# 3_waffling80-MX_mcu.net
KiCad netlist of a schematic drawn in Altium Designer
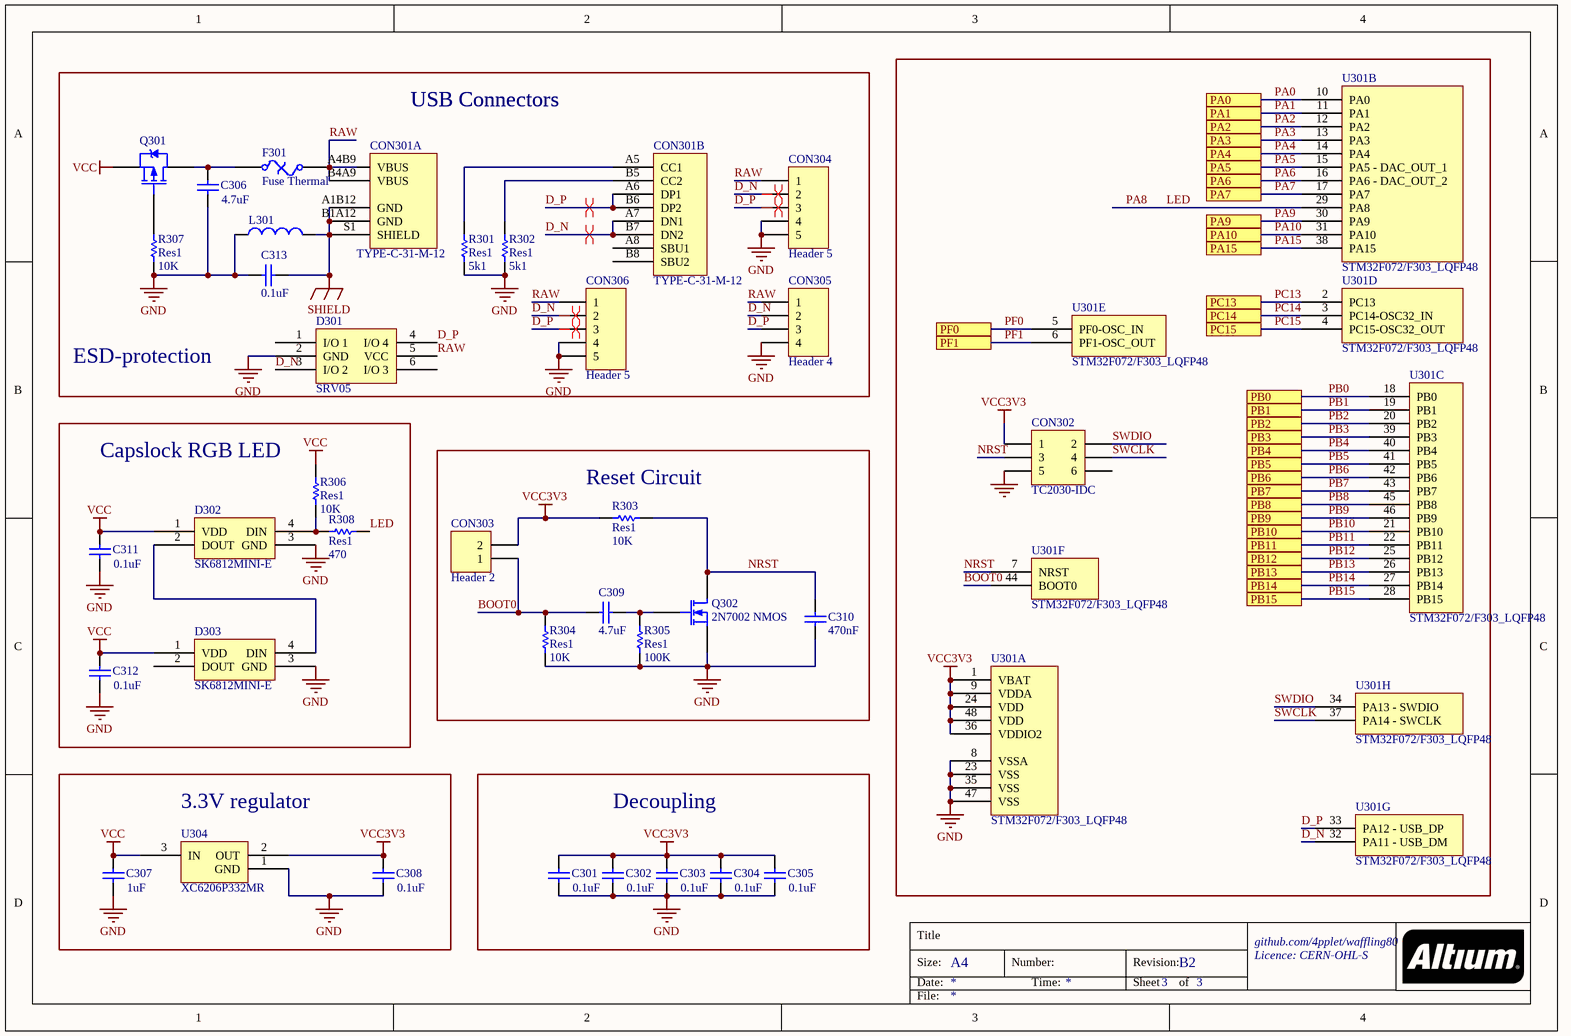
[diagram p0: 3_waffling80-MX_mcu.SchDoc]

(export (version "E")
  (design (tool "Eeschema 10.0.6"))
  (components
    (comp (ref "C301")
      (value "0.1uF")
      (footprint "C0603[1608]")
      (description "Capacitor")
      (fields (field (name "LCSC PART #") "C14663") (field (name "MRF.PART") "CC0603KRX7R9BB104"))
      (libsource (lib "Miscellaneous Devices") (part "Cap"))
    )
    (comp (ref "C302")
      (value "0.1uF")
      (footprint "C0603[1608]")
      (description "Capacitor")
      (fields (field (name "LCSC PART #") "C14663") (field (name "MRF.PART") "CC0603KRX7R9BB104"))
      (libsource (lib "Miscellaneous Devices") (part "Cap"))
    )
    (comp (ref "C303")
      (value "0.1uF")
      (footprint "C0603[1608]")
      (description "Capacitor")
      (fields (field (name "LCSC PART #") "C14663") (field (name "MRF.PART") "CC0603KRX7R9BB104"))
      (libsource (lib "Miscellaneous Devices") (part "Cap"))
    )
    (comp (ref "C304")
      (value "0.1uF")
      (footprint "C0603[1608]")
      (description "Capacitor")
      (fields (field (name "LCSC PART #") "C14663") (field (name "MRF.PART") "CC0603KRX7R9BB104"))
      (libsource (lib "Miscellaneous Devices") (part "Cap"))
    )
    (comp (ref "C305")
      (value "0.1uF")
      (footprint "C0603[1608]")
      (description "Capacitor")
      (fields (field (name "LCSC PART #") "C14663") (field (name "MRF.PART") "CC0603KRX7R9BB104"))
      (libsource (lib "Miscellaneous Devices") (part "Cap"))
    )
    (comp (ref "C306")
      (value "4.7uF")
      (footprint "C0603[1608]")
      (description "Capacitor")
      (fields (field (name "LCSC PART #") "C19666") (field (name "MRF.PART") "CL10A475KO8NNNC"))
      (libsource (lib "Miscellaneous Devices") (part "Cap"))
    )
    (comp (ref "C307")
      (value "1uF")
      (footprint "C0603[1608]")
      (description "Capacitor")
      (fields (field (name "LCSC PART #") "C15849") (field (name "MRF.PART") "CL10A105KB8NNNC"))
      (libsource (lib "Miscellaneous Devices") (part "Cap"))
    )
    (comp (ref "C308")
      (value "0.1uF")
      (footprint "C0603[1608]")
      (description "Capacitor")
      (fields (field (name "LCSC PART #") "C14663") (field (name "MRF.PART") "CC0603KRX7R9BB104"))
      (libsource (lib "Miscellaneous Devices") (part "Cap"))
    )
    (comp (ref "C309")
      (value "4.7uF")
      (footprint "C0603[1608]")
      (description "Capacitor")
      (fields (field (name "LCSC PART #") "C19666") (field (name "MRF.PART") "CL10A475KO8NNNC"))
      (libsource (lib "Miscellaneous Devices") (part "Cap"))
    )
    (comp (ref "C310")
      (value "470nF")
      (footprint "C0603[1608]")
      (description "Capacitor")
      (fields (field (name "LCSC PART #") "C1623") (field (name "MRF.PART") "CL10B474KA8NNNC"))
      (libsource (lib "Miscellaneous Devices") (part "Cap"))
    )
    (comp (ref "C311")
      (value "0.1uF")
      (footprint "C0603[1608]")
      (description "Capacitor")
      (fields (field (name "LCSC PART #") "C14663") (field (name "MRF.PART") "CC0603KRX7R9BB104"))
      (libsource (lib "Miscellaneous Devices") (part "Cap"))
    )
    (comp (ref "C312")
      (value "0.1uF")
      (footprint "C0603[1608]")
      (description "Capacitor")
      (fields (field (name "LCSC PART #") "C14663") (field (name "MRF.PART") "CC0603KRX7R9BB104"))
      (libsource (lib "Miscellaneous Devices") (part "Cap"))
    )
    (comp (ref "C313")
      (value "0.1uF")
      (footprint "C0603[1608]")
      (description "Capacitor")
      (fields (field (name "LCSC PART #") "C14663") (field (name "MRF.PART") "CC0603KRX7R9BB104"))
      (libsource (lib "Miscellaneous Devices") (part "Cap"))
    )
    (comp (ref "CON301")
      (value "TYPE-C-31-M-12")
      (footprint "TYPE-C-31-M-12")
      (fields (field (name "LCSC PART #") "C165948"))
      (libsource (lib "Schlib1") (part "TYPE-C-31-M-12"))
    )
    (comp (ref "CON302")
      (value "TC2030-IDC")
      (footprint "TC2030-IDC-NL")
      (description "Header, 3-Pin, Dual row")
      (libsource (lib "Miscellaneous Connectors") (part "Header 3X2"))
    )
    (comp (ref "CON303")
      (value "Header 2")
      (footprint "HDR1X2")
      (description "Header, 2-Pin")
      (libsource (lib "Miscellaneous Connectors") (part "Header 2"))
    )
    (comp (ref "CON304")
      (value "Header 5")
      (footprint "UDB_combo_JST_MOLEX")
      (description "JST for USB daughter board")
      (fields (field (name "LCSC PART #") "C160404") (field (name "MRF.PART") "SM04B-SRSS-TB(LF)(SN)"))
      (libsource (lib "Miscellaneous Connectors") (part "Header 5"))
    )
    (comp (ref "CON305")
      (value "Header 4")
      (footprint "HDR1X4")
      (description "Header, 4-Pin")
      (libsource (lib "Miscellaneous Connectors") (part "Header 4"))
    )
    (comp (ref "CON306")
      (value "Header 5")
      (footprint "Molex 781710004")
      (description "JST for USB daughter board")
      (fields (field (name "LCSC PART #") "C588524") (field (name "MRF.PART") "781710004"))
      (libsource (lib "Miscellaneous Connectors") (part "Header 5"))
    )
    (comp (ref "D301")
      (value "SRV05")
      (footprint "SOT-23-6")
      (fields (field (name "LCSC PART #") "C85364") (field (name "MRF.PART") "SRV05-4-P-T7"))
      (libsource (lib "Keebs") (part "SRV05"))
    )
    (comp (ref "D302")
      (value "SK6812MINI-E")
      (footprint "SK6812MINI-E - shaped")
      (fields (field (name "LCSC PART #") "C524051") (field (name "MRF.PART") "DY-S352818/RGBC/6812-2T"))
      (libsource (lib "Keebs") (part "SK6812MINI-E"))
    )
    (comp (ref "D303")
      (value "SK6812MINI-E")
      (footprint "SK6812MINI-E - shaped")
      (fields (field (name "LCSC PART #") "C524051") (field (name "MRF.PART") "DY-S352818/RGBC/6812-2T"))
      (libsource (lib "Keebs") (part "SK6812MINI-E"))
    )
    (comp (ref "F301")
      (value "Fuse Thermal")
      (footprint "C1206[3216]")
      (description "Thermal Fuse")
      (fields (field (name "LCSC PART #") "C135338") (field (name "MRF.PART") "ASMD1206-050"))
      (libsource (lib "Miscellaneous Devices") (part "Fuse Thermal"))
    )
    (comp (ref "L301")
      (value "Inductor")
      (footprint "L0805")
      (fields (field (name "LCSC PART #") "C1015") (field (name "MRF.PART") "GZ2012D101TF"))
      (libsource (lib "Simulation Generic Components") (part "Inductor"))
    )
    (comp (ref "Q301")
      (value "PMOS-2")
      (footprint "SOT-23-3")
      (description "P-Channel Power MOSFET")
      (fields (field (name "LCSC PART #") "C10487") (field (name "MRF.PART") "SI2301CDS-T1-GE3"))
      (libsource (lib "Miscellaneous Devices") (part "PMOS-2"))
    )
    (comp (ref "Q302")
      (value "2N7002 NMOS")
      (footprint "SOT-23-3")
      (description "N-Channel MOSFET")
      (fields (field (name "LCSC PART #") "C8545") (field (name "MRF.PART") "2N7002"))
      (libsource (lib "Miscellaneous Devices") (part "MOSFET-N"))
    )
    (comp (ref "R301")
      (value "Res1")
      (footprint "R0603[1608]")
      (description "Resistor")
      (fields
        (field (name "ALTIUM_VALUE") "5k1")
        (field (name "LCSC PART #") "C23186")
        (field (name "MRF.PART") "0603WAF5101T5E")
      )
      (libsource (lib "Miscellaneous Devices") (part "Res1"))
    )
    (comp (ref "R302")
      (value "Res1")
      (footprint "R0603[1608]")
      (description "Resistor")
      (fields
        (field (name "ALTIUM_VALUE") "5k1")
        (field (name "LCSC PART #") "C23186")
        (field (name "MRF.PART") "0603WAF5101T5E")
      )
      (libsource (lib "Miscellaneous Devices") (part "Res1"))
    )
    (comp (ref "R303")
      (value "Res1")
      (footprint "R0603[1608]")
      (description "Resistor")
      (fields
        (field (name "ALTIUM_VALUE") "10K")
        (field (name "LCSC PART #") "C25804")
        (field (name "MRF.PART") "0603WAF1002T5E")
      )
      (libsource (lib "Miscellaneous Devices") (part "Res1"))
    )
    (comp (ref "R304")
      (value "Res1")
      (footprint "R0603[1608]")
      (description "Resistor")
      (fields
        (field (name "ALTIUM_VALUE") "10K")
        (field (name "LCSC PART #") "C25804")
        (field (name "MRF.PART") "0603WAF1002T5E")
      )
      (libsource (lib "Miscellaneous Devices") (part "Res1"))
    )
    (comp (ref "R305")
      (value "Res1")
      (footprint "R0603[1608]")
      (description "Resistor")
      (fields
        (field (name "ALTIUM_VALUE") "100K")
        (field (name "LCSC PART #") "C25803")
        (field (name "MRF.PART") "0603WAF1003T5E")
      )
      (libsource (lib "Miscellaneous Devices") (part "Res1"))
    )
    (comp (ref "R306")
      (value "Res1")
      (footprint "R0603[1608]")
      (description "Resistor")
      (fields
        (field (name "ALTIUM_VALUE") "10K")
        (field (name "LCSC PART #") "C25804")
        (field (name "MRF.PART") "0603WAF1002T5E")
      )
      (libsource (lib "Miscellaneous Devices") (part "Res1"))
    )
    (comp (ref "R307")
      (value "Res1")
      (footprint "R0603[1608]")
      (description "Resistor")
      (fields
        (field (name "ALTIUM_VALUE") "10K")
        (field (name "LCSC PART #") "C25804")
        (field (name "MRF.PART") "0603WAF1002T5E")
      )
      (libsource (lib "Miscellaneous Devices") (part "Res1"))
    )
    (comp (ref "R308")
      (value "Res1")
      (footprint "R0603[1608]")
      (description "Resistor")
      (fields
        (field (name "ALTIUM_VALUE") "470")
        (field (name "LCSC PART #") "C23179")
        (field (name "MRF.PART") "0603WAF4700T5E")
      )
      (libsource (lib "Miscellaneous Devices") (part "Res1"))
    )
    (comp (ref "U301")
      (value "STM32F072/F303_LQFP48")
      (footprint "STM32 - COMBO 7X7MM")
      (fields (field (name "LCSC PART #") "C915660") (field (name "MRF.PART") "APM32F072CBT6"))
      (libsource (lib "Keebs") (part "STM32F072/F303_LQFP48"))
    )
    (comp (ref "U304")
      (value "XC6206P332MR")
      (footprint "SOT-23-3")
      (fields (field (name "LCSC PART #") "C5446"))
      (libsource (lib "Keebs") (part "SOT23 LDO"))
    )
  )
  (nets
    (net (code "1") (name "/BOOT0") (class "Default")
      (node (ref "C309") (pin "1") (pinfunction "1_1") (pintype "passive"))
      (node (ref "CON303") (pin "1") (pinfunction "1_1") (pintype "passive"))
      (node (ref "R304") (pin "1") (pinfunction "1_1") (pintype "passive"))
      (node (ref "U301") (pin "44") (pinfunction "BOOT0_44") (pintype "passive"))
    )
    (net (code "2") (name "/D_N") (class "Default")
      (node (ref "CON301") (pin "A7") (pinfunction "DN1_A7") (pintype "passive"))
      (node (ref "CON301") (pin "B7") (pinfunction "DN2_B7") (pintype "passive"))
      (node (ref "CON304") (pin "2") (pinfunction "2_2") (pintype "passive"))
      (node (ref "CON305") (pin "2") (pinfunction "2_2") (pintype "passive"))
      (node (ref "CON306") (pin "2") (pinfunction "2_2") (pintype "passive"))
      (node (ref "D301") (pin "3") (pinfunction "I/O_2_3") (pintype "passive"))
      (node (ref "U301") (pin "32") (pinfunction "PA11_-_USB_DM_32") (pintype "passive"))
    )
    (net (code "3") (name "/D_P") (class "Default")
      (node (ref "CON301") (pin "A6") (pinfunction "DP1_A6") (pintype "passive"))
      (node (ref "CON301") (pin "B6") (pinfunction "DP2_B6") (pintype "passive"))
      (node (ref "CON304") (pin "3") (pinfunction "3_3") (pintype "passive"))
      (node (ref "CON305") (pin "3") (pinfunction "3_3") (pintype "passive"))
      (node (ref "CON306") (pin "3") (pinfunction "3_3") (pintype "passive"))
      (node (ref "D301") (pin "4") (pinfunction "I/O_4_4") (pintype "passive"))
      (node (ref "U301") (pin "33") (pinfunction "PA12_-_USB_DP_33") (pintype "passive"))
    )
    (net (code "4") (name "/LED") (class "Default")
      (node (ref "R308") (pin "2") (pinfunction "2_2") (pintype "passive"))
      (node (ref "U301") (pin "29") (pinfunction "PA8_29") (pintype "passive"))
    )
    (net (code "5") (name "/NRST") (class "Default")
      (node (ref "C310") (pin "1") (pinfunction "1_1") (pintype "passive"))
      (node (ref "CON302") (pin "3") (pinfunction "3_3") (pintype "passive"))
      (node (ref "Q302") (pin "3") (pinfunction "D_3") (pintype "passive"))
      (node (ref "R303") (pin "2") (pinfunction "2_2") (pintype "passive"))
      (node (ref "U301") (pin "7") (pinfunction "NRST_7") (pintype "passive"))
    )
    (net (code "6") (name "/PA0") (class "Default")
      (node (ref "U301") (pin "10") (pinfunction "PA0_10") (pintype "passive"))
    )
    (net (code "7") (name "/PA1") (class "Default")
      (node (ref "U301") (pin "11") (pinfunction "PA1_11") (pintype "passive"))
    )
    (net (code "8") (name "/PA2") (class "Default")
      (node (ref "U301") (pin "12") (pinfunction "PA2_12") (pintype "passive"))
    )
    (net (code "9") (name "/PA3") (class "Default")
      (node (ref "U301") (pin "13") (pinfunction "PA3_13") (pintype "passive"))
    )
    (net (code "10") (name "/PA4") (class "Default")
      (node (ref "U301") (pin "14") (pinfunction "PA4_14") (pintype "passive"))
    )
    (net (code "11") (name "/PA5") (class "Default")
      (node (ref "U301") (pin "15") (pinfunction "PA5_-_DAC_OUT_1_15") (pintype "passive"))
    )
    (net (code "12") (name "/PA6") (class "Default")
      (node (ref "U301") (pin "16") (pinfunction "PA6_-_DAC_OUT_2_16") (pintype "passive"))
    )
    (net (code "13") (name "/PA7") (class "Default")
      (node (ref "U301") (pin "17") (pinfunction "PA7_17") (pintype "passive"))
    )
    (net (code "14") (name "/PA9") (class "Default")
      (node (ref "U301") (pin "30") (pinfunction "PA9_30") (pintype "passive"))
    )
    (net (code "15") (name "/PA10") (class "Default")
      (node (ref "U301") (pin "31") (pinfunction "PA10_31") (pintype "passive"))
    )
    (net (code "16") (name "/PA15") (class "Default")
      (node (ref "U301") (pin "38") (pinfunction "PA15_38") (pintype "passive"))
    )
    (net (code "17") (name "/PB0") (class "Default")
      (node (ref "U301") (pin "18") (pinfunction "PB0_18") (pintype "passive"))
    )
    (net (code "18") (name "/PB1") (class "Default")
      (node (ref "U301") (pin "19") (pinfunction "PB1_19") (pintype "passive"))
    )
    (net (code "19") (name "/PB2") (class "Default")
      (node (ref "U301") (pin "20") (pinfunction "PB2_20") (pintype "passive"))
    )
    (net (code "20") (name "/PB3") (class "Default")
      (node (ref "U301") (pin "39") (pinfunction "PB3_39") (pintype "passive"))
    )
    (net (code "21") (name "/PB4") (class "Default")
      (node (ref "U301") (pin "40") (pinfunction "PB4_40") (pintype "passive"))
    )
    (net (code "22") (name "/PB5") (class "Default")
      (node (ref "U301") (pin "41") (pinfunction "PB5_41") (pintype "passive"))
    )
    (net (code "23") (name "/PB6") (class "Default")
      (node (ref "U301") (pin "42") (pinfunction "PB6_42") (pintype "passive"))
    )
    (net (code "24") (name "/PB7") (class "Default")
      (node (ref "U301") (pin "43") (pinfunction "PB7_43") (pintype "passive"))
    )
    (net (code "25") (name "/PB8") (class "Default")
      (node (ref "U301") (pin "45") (pinfunction "PB8_45") (pintype "passive"))
    )
    (net (code "26") (name "/PB9") (class "Default")
      (node (ref "U301") (pin "46") (pinfunction "PB9_46") (pintype "passive"))
    )
    (net (code "27") (name "/PB10") (class "Default")
      (node (ref "U301") (pin "21") (pinfunction "PB10_21") (pintype "passive"))
    )
    (net (code "28") (name "/PB11") (class "Default")
      (node (ref "U301") (pin "22") (pinfunction "PB11_22") (pintype "passive"))
    )
    (net (code "29") (name "/PB12") (class "Default")
      (node (ref "U301") (pin "25") (pinfunction "PB12_25") (pintype "passive"))
    )
    (net (code "30") (name "/PB13") (class "Default")
      (node (ref "U301") (pin "26") (pinfunction "PB13_26") (pintype "passive"))
    )
    (net (code "31") (name "/PB14") (class "Default")
      (node (ref "U301") (pin "27") (pinfunction "PB14_27") (pintype "passive"))
    )
    (net (code "32") (name "/PB15") (class "Default")
      (node (ref "U301") (pin "28") (pinfunction "PB15_28") (pintype "passive"))
    )
    (net (code "33") (name "/PC13") (class "Default")
      (node (ref "U301") (pin "2") (pinfunction "PC13_2") (pintype "passive"))
    )
    (net (code "34") (name "/PC14") (class "Default")
      (node (ref "U301") (pin "3") (pinfunction "PC14-OSC32_IN_3") (pintype "passive"))
    )
    (net (code "35") (name "/PC15") (class "Default")
      (node (ref "U301") (pin "4") (pinfunction "PC15-OSC32_OUT_4") (pintype "passive"))
    )
    (net (code "36") (name "/PF0") (class "Default")
      (node (ref "U301") (pin "5") (pinfunction "PF0-OSC_IN_5") (pintype "passive"))
    )
    (net (code "37") (name "/PF1") (class "Default")
      (node (ref "U301") (pin "6") (pinfunction "PF1-OSC_OUT_6") (pintype "passive"))
    )
    (net (code "38") (name "/RAW") (class "Default")
      (node (ref "CON301") (pin "A4B9") (pinfunction "VBUS_A4B9") (pintype "passive"))
      (node (ref "CON301") (pin "B4A9") (pinfunction "VBUS_B4A9") (pintype "passive"))
      (node (ref "CON304") (pin "1") (pinfunction "1_1") (pintype "passive"))
      (node (ref "CON305") (pin "1") (pinfunction "1_1") (pintype "passive"))
      (node (ref "CON306") (pin "1") (pinfunction "1_1") (pintype "passive"))
      (node (ref "D301") (pin "5") (pinfunction "VCC_5") (pintype "passive"))
      (node (ref "F301") (pin "2") (pinfunction "2_2") (pintype "passive"))
    )
    (net (code "39") (name "/SWCLK") (class "Default")
      (node (ref "CON302") (pin "4") (pinfunction "4_4") (pintype "passive"))
      (node (ref "U301") (pin "37") (pinfunction "PA14_-_SWCLK_37") (pintype "passive"))
    )
    (net (code "40") (name "/SWDIO") (class "Default")
      (node (ref "CON302") (pin "2") (pinfunction "2_2") (pintype "passive"))
      (node (ref "U301") (pin "34") (pinfunction "PA13_-_SWDIO_34") (pintype "passive"))
    )
    (net (code "41") (name "GND") (class "Default")
      (node (ref "C301") (pin "1") (pinfunction "1_1") (pintype "passive"))
      (node (ref "C302") (pin "1") (pinfunction "1_1") (pintype "passive"))
      (node (ref "C303") (pin "1") (pinfunction "1_1") (pintype "passive"))
      (node (ref "C304") (pin "1") (pinfunction "1_1") (pintype "passive"))
      (node (ref "C305") (pin "1") (pinfunction "1_1") (pintype "passive"))
      (node (ref "C306") (pin "1") (pinfunction "1_1") (pintype "passive"))
      (node (ref "C307") (pin "1") (pinfunction "1_1") (pintype "passive"))
      (node (ref "C308") (pin "1") (pinfunction "1_1") (pintype "passive"))
      (node (ref "C310") (pin "2") (pinfunction "2_2") (pintype "passive"))
      (node (ref "C311") (pin "1") (pinfunction "1_1") (pintype "passive"))
      (node (ref "C312") (pin "1") (pinfunction "1_1") (pintype "passive"))
      (node (ref "C313") (pin "1") (pinfunction "1_1") (pintype "passive"))
      (node (ref "CON302") (pin "5") (pinfunction "5_5") (pintype "passive"))
      (node (ref "CON304") (pin "4") (pinfunction "4_4") (pintype "passive"))
      (node (ref "CON304") (pin "5") (pinfunction "5_5") (pintype "passive"))
      (node (ref "CON305") (pin "4") (pinfunction "4_4") (pintype "passive"))
      (node (ref "CON306") (pin "4") (pinfunction "4_4") (pintype "passive"))
      (node (ref "CON306") (pin "5") (pinfunction "5_5") (pintype "passive"))
      (node (ref "D301") (pin "2") (pinfunction "GND_2") (pintype "passive"))
      (node (ref "D302") (pin "3") (pinfunction "GND_3") (pintype "passive"))
      (node (ref "D303") (pin "3") (pinfunction "GND_3") (pintype "passive"))
      (node (ref "L301") (pin "1") (pinfunction "1_1") (pintype "passive"))
      (node (ref "Q302") (pin "2") (pinfunction "S_2") (pintype "passive"))
      (node (ref "R301") (pin "2") (pinfunction "2_2") (pintype "passive"))
      (node (ref "R302") (pin "2") (pinfunction "2_2") (pintype "passive"))
      (node (ref "R304") (pin "2") (pinfunction "2_2") (pintype "passive"))
      (node (ref "R305") (pin "2") (pinfunction "2_2") (pintype "passive"))
      (node (ref "R307") (pin "2") (pinfunction "2_2") (pintype "passive"))
      (node (ref "U301") (pin "23") (pinfunction "VSS_23") (pintype "passive"))
      (node (ref "U301") (pin "35") (pinfunction "VSS_35") (pintype "passive"))
      (node (ref "U301") (pin "47") (pinfunction "VSS_47") (pintype "passive"))
      (node (ref "U301") (pin "8") (pinfunction "VSSA_8") (pintype "passive"))
      (node (ref "U304") (pin "1") (pinfunction "GND_1") (pintype "passive"))
    )
    (net (code "42") (name "Net-(CON301B-CC1)") (class "Default")
      (node (ref "CON301") (pin "A5") (pinfunction "CC1_A5") (pintype "passive"))
      (node (ref "R301") (pin "1") (pinfunction "1_1") (pintype "passive"))
    )
    (net (code "43") (name "Net-(CON301B-CC2)") (class "Default")
      (node (ref "CON301") (pin "B5") (pinfunction "CC2_B5") (pintype "passive"))
      (node (ref "R302") (pin "1") (pinfunction "1_1") (pintype "passive"))
    )
    (net (code "44") (name "Net-(D302-DIN)") (class "Default")
      (node (ref "D302") (pin "4") (pinfunction "DIN_4") (pintype "passive"))
      (node (ref "R306") (pin "2") (pinfunction "2_2") (pintype "passive"))
      (node (ref "R308") (pin "1") (pinfunction "1_1") (pintype "passive"))
    )
    (net (code "45") (name "Net-(D302-DOUT)") (class "Default")
      (node (ref "D302") (pin "2") (pinfunction "DOUT_2") (pintype "passive"))
      (node (ref "D303") (pin "4") (pinfunction "DIN_4") (pintype "passive"))
    )
    (net (code "46") (name "Net-(Q301-D)") (class "Default")
      (node (ref "C306") (pin "2") (pinfunction "2_2") (pintype "passive"))
      (node (ref "F301") (pin "1") (pinfunction "1_1") (pintype "passive"))
      (node (ref "Q301") (pin "3") (pinfunction "D_3") (pintype "passive"))
    )
    (net (code "47") (name "Net-(Q301-G)") (class "Default")
      (node (ref "Q301") (pin "1") (pinfunction "G_1") (pintype "passive"))
      (node (ref "R307") (pin "1") (pinfunction "1_1") (pintype "passive"))
    )
    (net (code "48") (name "Net-(Q302-G)") (class "Default")
      (node (ref "C309") (pin "2") (pinfunction "2_2") (pintype "passive"))
      (node (ref "Q302") (pin "1") (pinfunction "G_1") (pintype "passive"))
      (node (ref "R305") (pin "1") (pinfunction "1_1") (pintype "passive"))
    )
    (net (code "49") (name "SHIELD") (class "Default")
      (node (ref "C313") (pin "2") (pinfunction "2_2") (pintype "passive"))
      (node (ref "CON301") (pin "A1B12") (pinfunction "GND_A1B12") (pintype "passive"))
      (node (ref "CON301") (pin "B1A12") (pinfunction "GND_B1A12") (pintype "passive"))
      (node (ref "CON301") (pin "S1") (pinfunction "SHIELD_S1") (pintype "passive"))
      (node (ref "L301") (pin "2") (pinfunction "2_2") (pintype "passive"))
    )
    (net (code "50") (name "VCC") (class "Default")
      (node (ref "C307") (pin "2") (pinfunction "2_2") (pintype "passive"))
      (node (ref "C311") (pin "2") (pinfunction "2_2") (pintype "passive"))
      (node (ref "C312") (pin "2") (pinfunction "2_2") (pintype "passive"))
      (node (ref "D302") (pin "1") (pinfunction "VDD_1") (pintype "passive"))
      (node (ref "D303") (pin "1") (pinfunction "VDD_1") (pintype "passive"))
      (node (ref "Q301") (pin "2") (pinfunction "S_2") (pintype "passive"))
      (node (ref "R306") (pin "1") (pinfunction "1_1") (pintype "passive"))
      (node (ref "U304") (pin "3") (pinfunction "IN_3") (pintype "passive"))
    )
    (net (code "51") (name "VCC3V3") (class "Default")
      (node (ref "C301") (pin "2") (pinfunction "2_2") (pintype "passive"))
      (node (ref "C302") (pin "2") (pinfunction "2_2") (pintype "passive"))
      (node (ref "C303") (pin "2") (pinfunction "2_2") (pintype "passive"))
      (node (ref "C304") (pin "2") (pinfunction "2_2") (pintype "passive"))
      (node (ref "C305") (pin "2") (pinfunction "2_2") (pintype "passive"))
      (node (ref "C308") (pin "2") (pinfunction "2_2") (pintype "passive"))
      (node (ref "CON302") (pin "1") (pinfunction "1_1") (pintype "passive"))
      (node (ref "CON303") (pin "2") (pinfunction "2_2") (pintype "passive"))
      (node (ref "R303") (pin "1") (pinfunction "1_1") (pintype "passive"))
      (node (ref "U301") (pin "1") (pinfunction "VBAT_1") (pintype "passive"))
      (node (ref "U301") (pin "24") (pinfunction "VDD_24") (pintype "passive"))
      (node (ref "U301") (pin "36") (pinfunction "VDDIO2_36") (pintype "passive"))
      (node (ref "U301") (pin "48") (pinfunction "VDD_48") (pintype "passive"))
      (node (ref "U301") (pin "9") (pinfunction "VDDA_9") (pintype "passive"))
      (node (ref "U304") (pin "2") (pinfunction "OUT_2") (pintype "passive"))
    )
    (net (code "52") (name "unconnected-(CON301B-SBU1-PadA8)") (class "Default")
      (node (ref "CON301") (pin "A8") (pinfunction "SBU1_A8") (pintype "passive"))
    )
    (net (code "53") (name "unconnected-(CON301B-SBU2-PadB8)") (class "Default")
      (node (ref "CON301") (pin "B8") (pinfunction "SBU2_B8") (pintype "passive"))
    )
    (net (code "54") (name "unconnected-(CON302-Pad6)") (class "Default")
      (node (ref "CON302") (pin "6") (pinfunction "6_6") (pintype "passive"))
    )
    (net (code "55") (name "unconnected-(D301-I{slash}O_1-Pad1)") (class "Default")
      (node (ref "D301") (pin "1") (pinfunction "I/O_1_1") (pintype "passive"))
    )
    (net (code "56") (name "unconnected-(D301-I{slash}O_3-Pad6)") (class "Default")
      (node (ref "D301") (pin "6") (pinfunction "I/O_3_6") (pintype "passive"))
    )
    (net (code "57") (name "unconnected-(D303-DOUT-Pad2)") (class "Default")
      (node (ref "D303") (pin "2") (pinfunction "DOUT_2") (pintype "passive"))
    )
  )
)
